# TOP.net
KiCad netlist of a schematic drawn in Altium Designer
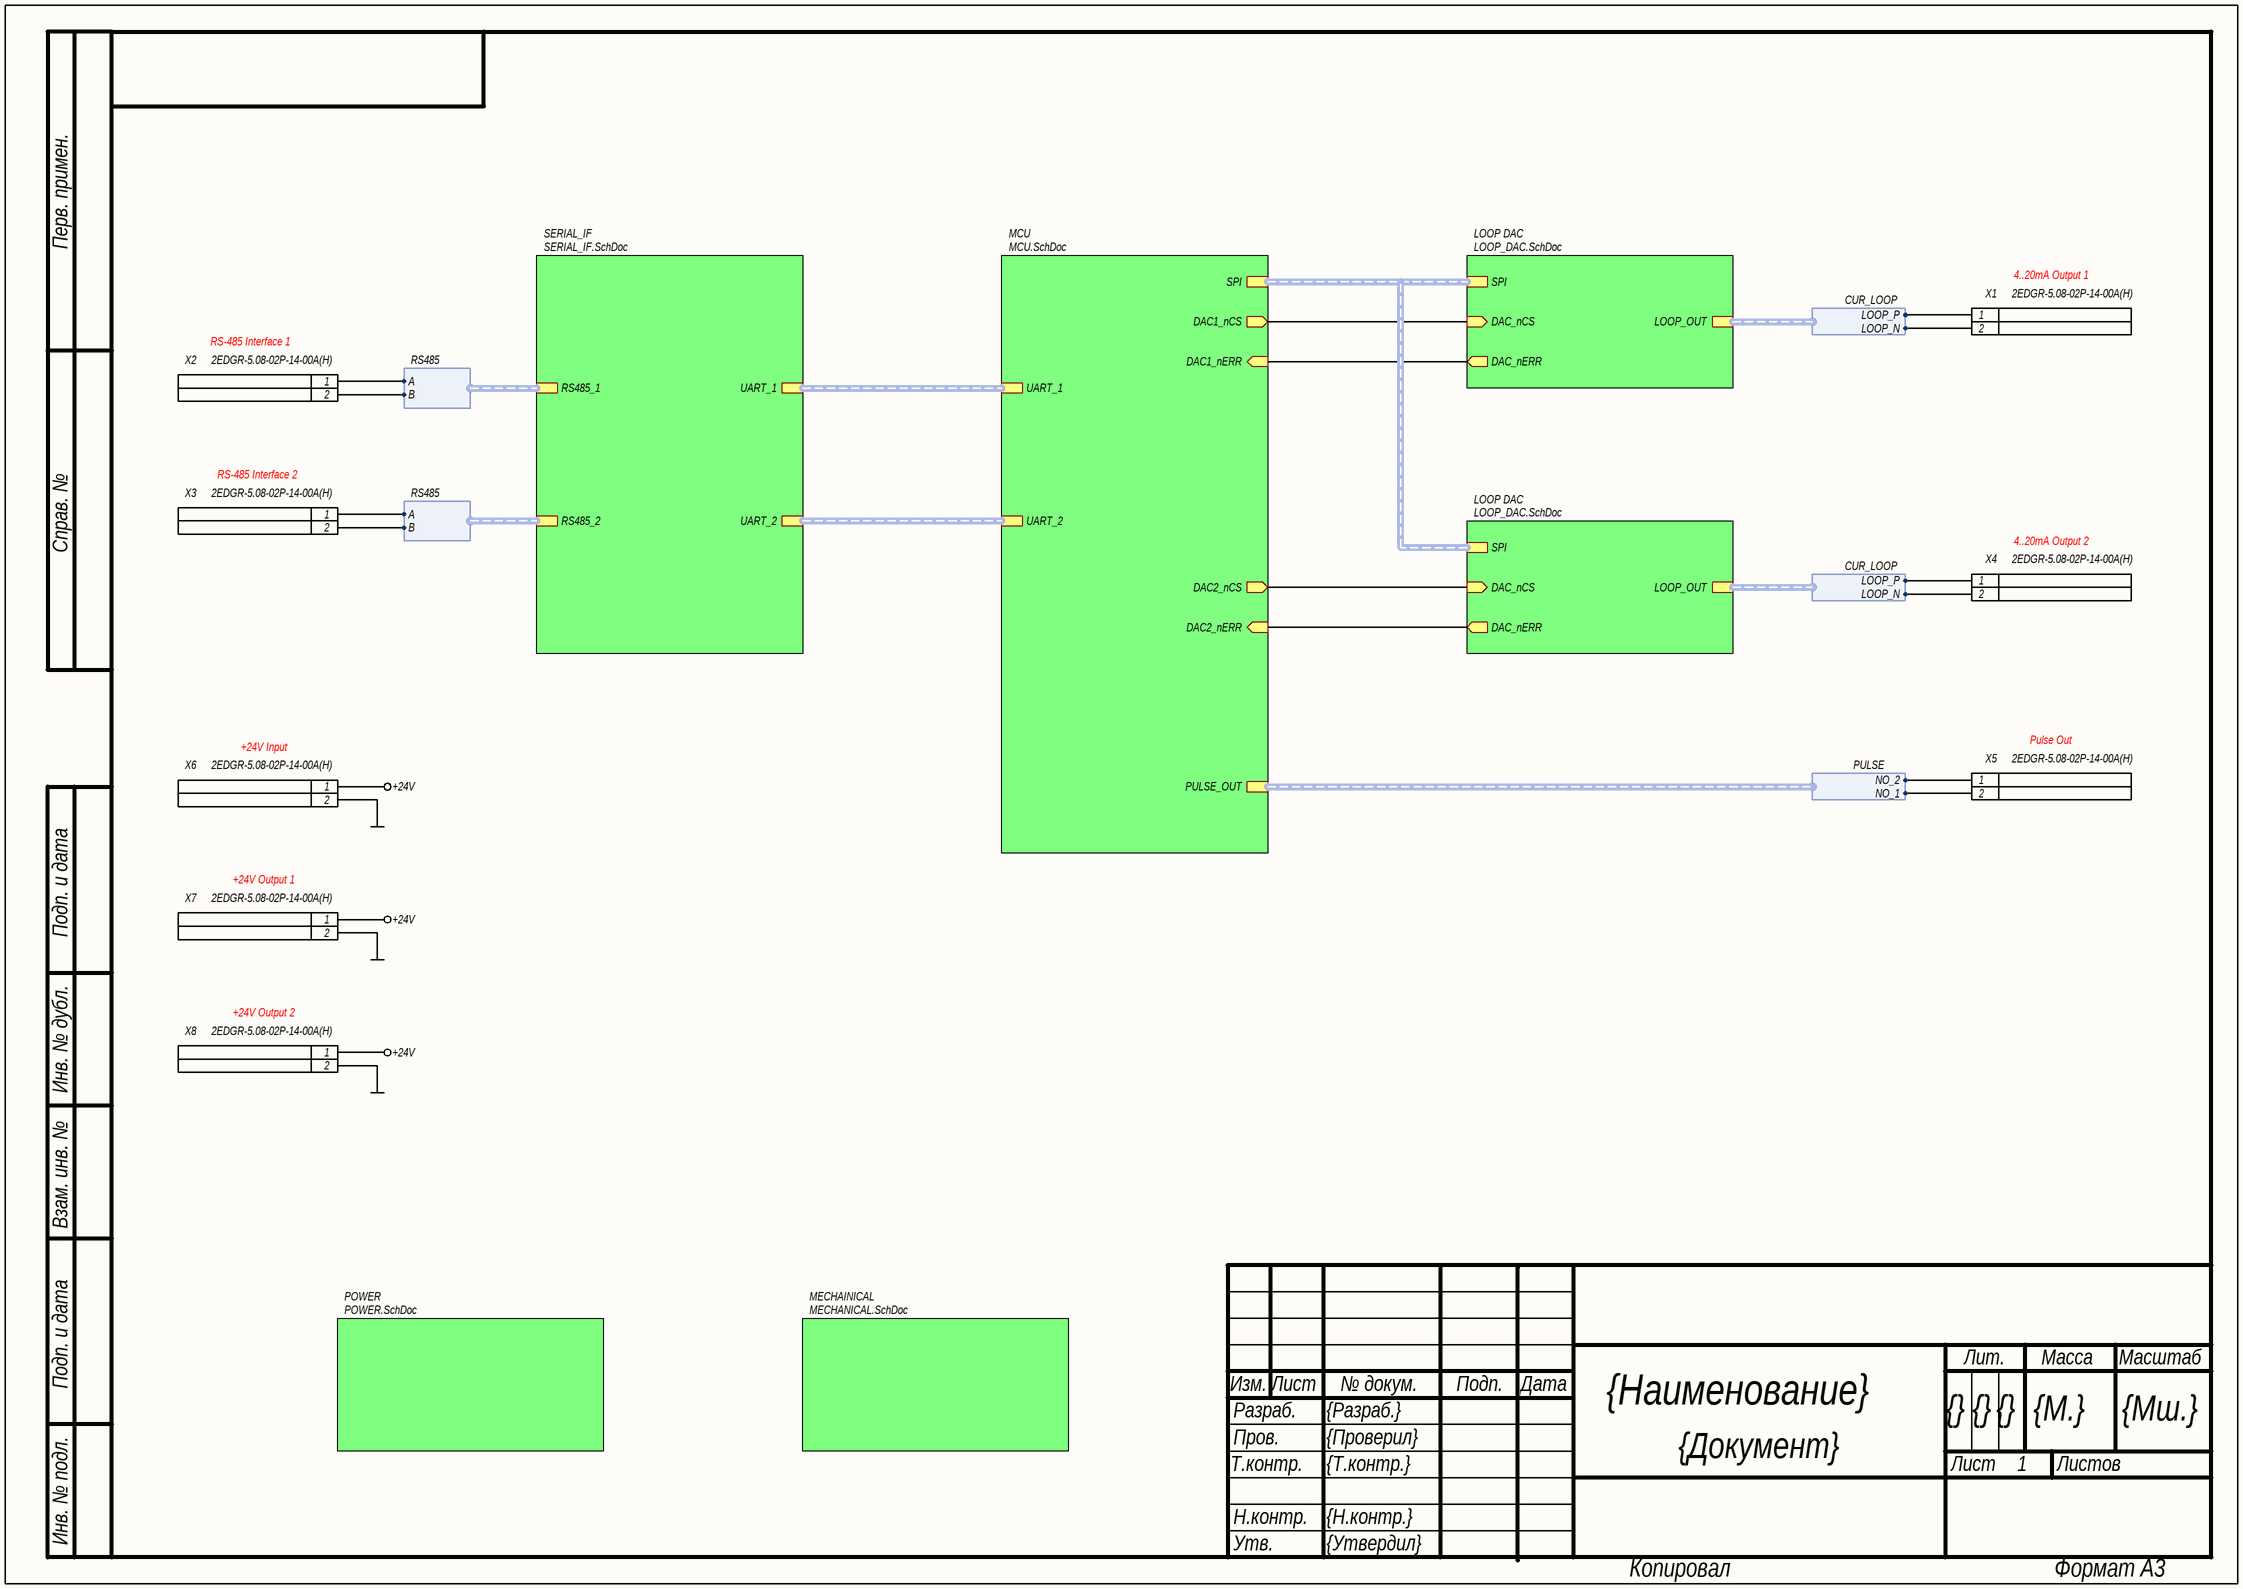
[diagram p0: TOP.SchDoc]

(export (version "E")
  (design (tool "Eeschema 10.0.6"))
  (components
    (comp (ref "X1")
      (value "2EDGR-5.08-02P-14-00A(H)")
      (footprint "2EDGR-5.08-02P-14-00A(H)")
      (description "Разъем, 2 контакта")
      (libsource (lib "Components Library") (part "Connector 2"))
    )
    (comp (ref "X2")
      (value "2EDGR-5.08-02P-14-00A(H)")
      (footprint "2EDGR-5.08-02P-14-00A(H)")
      (description "Разъем, 2 контакта")
      (libsource (lib "Components Library") (part "Connector 2"))
    )
    (comp (ref "X3")
      (value "2EDGR-5.08-02P-14-00A(H)")
      (footprint "2EDGR-5.08-02P-14-00A(H)")
      (description "Разъем, 2 контакта")
      (libsource (lib "Components Library") (part "Connector 2"))
    )
    (comp (ref "X4")
      (value "2EDGR-5.08-02P-14-00A(H)")
      (footprint "2EDGR-5.08-02P-14-00A(H)")
      (description "Разъем, 2 контакта")
      (libsource (lib "Components Library") (part "Connector 2"))
    )
    (comp (ref "X5")
      (value "2EDGR-5.08-02P-14-00A(H)")
      (footprint "2EDGR-5.08-02P-14-00A(H)")
      (description "Разъем, 2 контакта")
      (libsource (lib "Components Library") (part "Connector 2"))
    )
    (comp (ref "X6")
      (value "2EDGR-5.08-02P-14-00A(H)")
      (footprint "2EDGR-5.08-02P-14-00A(H)")
      (description "Разъем, 2 контакта")
      (libsource (lib "Components Library") (part "Connector 2"))
    )
    (comp (ref "X7")
      (value "2EDGR-5.08-02P-14-00A(H)")
      (footprint "2EDGR-5.08-02P-14-00A(H)")
      (description "Разъем, 2 контакта")
      (libsource (lib "Components Library") (part "Connector 2"))
    )
    (comp (ref "X8")
      (value "2EDGR-5.08-02P-14-00A(H)")
      (footprint "2EDGR-5.08-02P-14-00A(H)")
      (description "Разъем, 2 контакта")
      (libsource (lib "Components Library") (part "Connector 2"))
    )
  )
  (nets
    (net (code "4") (name "+24V") (class "Default")
      (node (ref "X6") (pin "1") (pinfunction "1_1") (pintype "power_in"))
      (node (ref "X7") (pin "1") (pinfunction "1_1") (pintype "power_in"))
      (node (ref "X8") (pin "1") (pinfunction "1_1") (pintype "power_in"))
    )
    (net (code "9") (name "/NO_1") (class "Default")
      (node (ref "X5") (pin "2") (pinfunction "2_2") (pintype "power_in"))
    )
    (net (code "10") (name "/NO_2") (class "Default")
      (node (ref "X5") (pin "1") (pinfunction "1_1") (pintype "power_in"))
    )
    (net (code "17") (name "GND") (class "Default")
      (node (ref "X6") (pin "2") (pinfunction "2_2") (pintype "power_in"))
      (node (ref "X7") (pin "2") (pinfunction "2_2") (pintype "power_in"))
      (node (ref "X8") (pin "2") (pinfunction "2_2") (pintype "power_in"))
    )
    (net (code "18") (name "unconnected-(X1-Pad1)") (class "Default")
      (node (ref "X1") (pin "1") (pinfunction "1_1") (pintype "power_in"))
    )
    (net (code "19") (name "unconnected-(X1-Pad2)") (class "Default")
      (node (ref "X1") (pin "2") (pinfunction "2_2") (pintype "power_in"))
    )
    (net (code "20") (name "unconnected-(X2-Pad1)") (class "Default")
      (node (ref "X2") (pin "1") (pinfunction "1_1") (pintype "power_in"))
    )
    (net (code "21") (name "unconnected-(X2-Pad2)") (class "Default")
      (node (ref "X2") (pin "2") (pinfunction "2_2") (pintype "power_in"))
    )
    (net (code "22") (name "unconnected-(X3-Pad1)") (class "Default")
      (node (ref "X3") (pin "1") (pinfunction "1_1") (pintype "power_in"))
    )
    (net (code "23") (name "unconnected-(X3-Pad2)") (class "Default")
      (node (ref "X3") (pin "2") (pinfunction "2_2") (pintype "power_in"))
    )
    (net (code "24") (name "unconnected-(X4-Pad1)") (class "Default")
      (node (ref "X4") (pin "1") (pinfunction "1_1") (pintype "power_in"))
    )
    (net (code "25") (name "unconnected-(X4-Pad2)") (class "Default")
      (node (ref "X4") (pin "2") (pinfunction "2_2") (pintype "power_in"))
    )
  )
)
